# fishnet-0_1.net
KiCad netlist of a schematic drawn in EAGLE
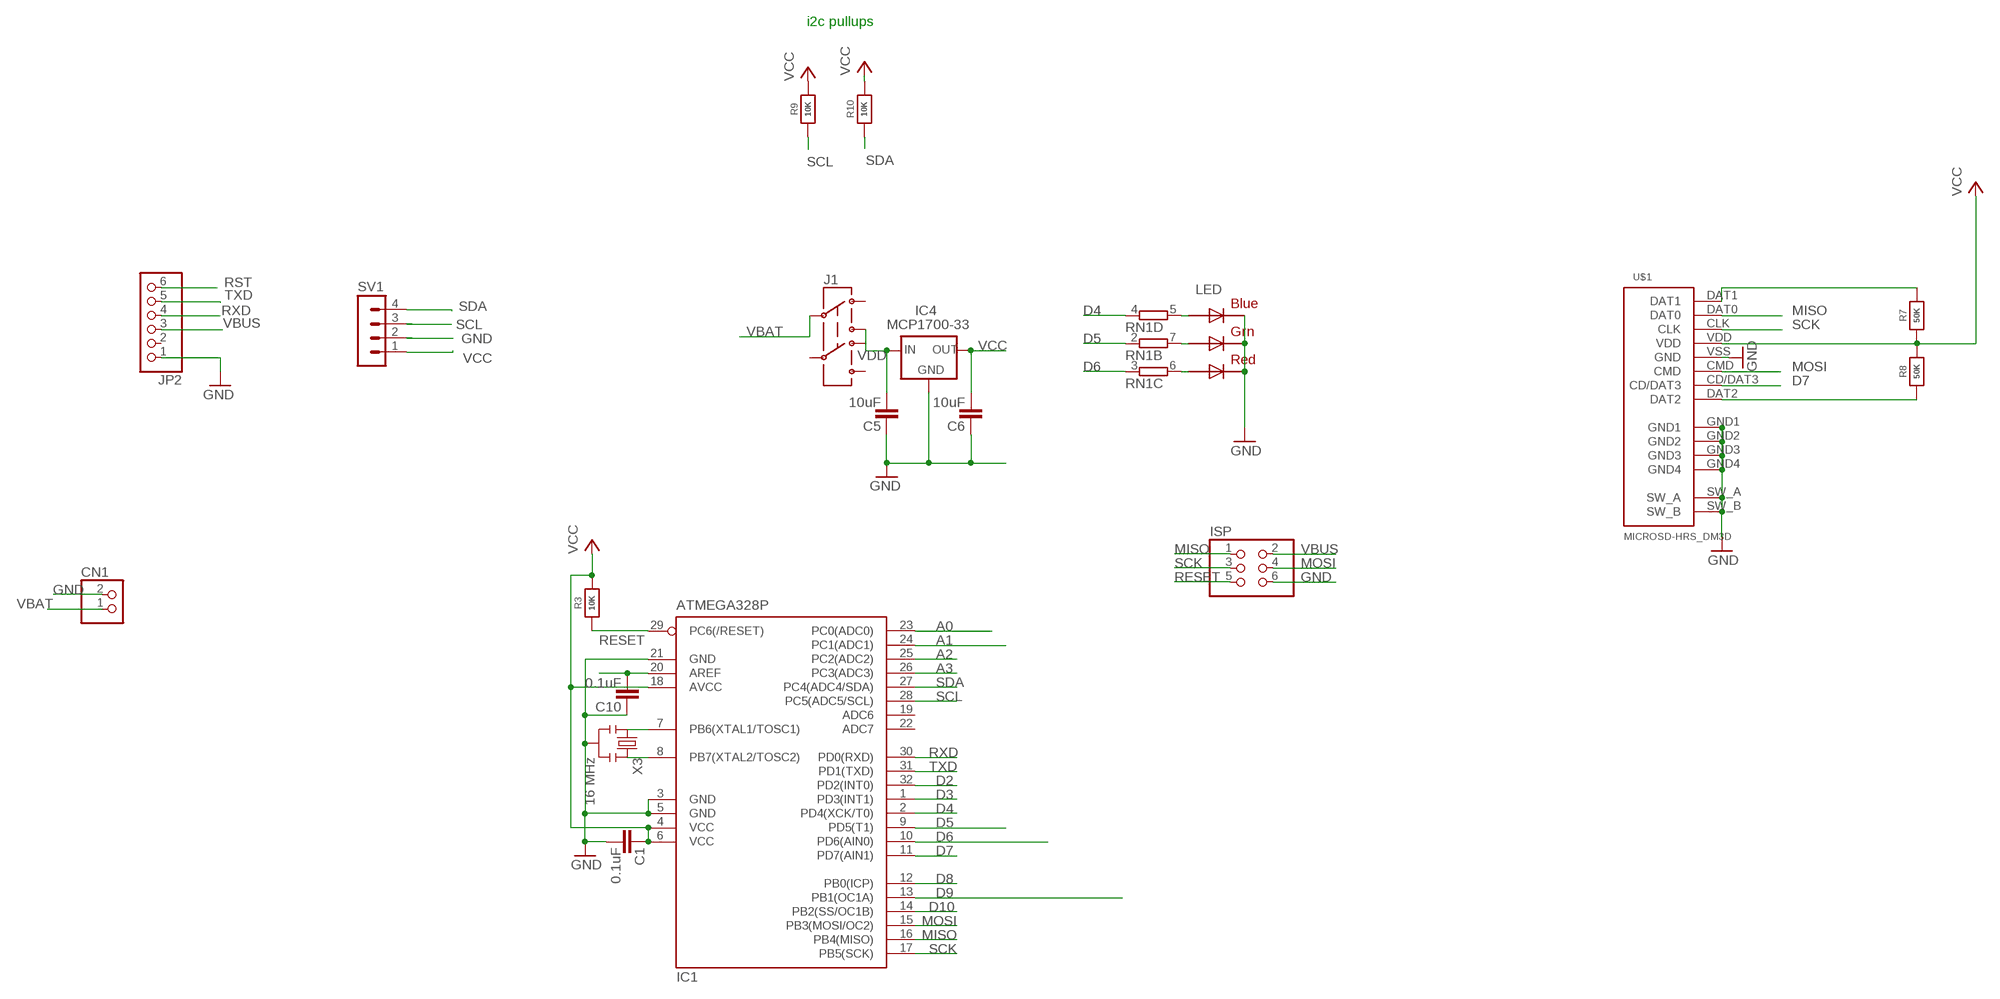
[diagram p0: schematic, sheet 1]

(export (version "E")
  (design (tool "Eeschema 10.0.6"))
  (components
    (comp (ref "C1")
      (value "0.1uF")
      (footprint "eagle-import:0603-CAP")
      (libsource (lib "eagle-import") (part "CAP0603-CAP"))
    )
    (comp (ref "C5")
      (value "10uF")
      (footprint "eagle-import:0603-CAP")
      (libsource (lib "eagle-import") (part "CAP0603-CAP"))
    )
    (comp (ref "C6")
      (value "10uF")
      (footprint "eagle-import:0603-CAP")
      (libsource (lib "eagle-import") (part "CAP0603-CAP"))
    )
    (comp (ref "C10")
      (value "0.1uF")
      (footprint "eagle-import:0603-CAP")
      (libsource (lib "eagle-import") (part "CAP0603-CAP"))
    )
    (comp (ref "CN1")
      (value "JST_2PIN-SMT-RA")
      (footprint "eagle-import:JST-PH-2-SMT-RA")
      (libsource (lib "eagle-import") (part "JST_2PIN-SMT-RA"))
    )
    (comp (ref "IC1")
      (value "ATMEGA328P")
      (footprint "eagle-import:TQFP32-08")
      (fields (field (name "MPN") "ATMEGA8-16AU"))
      (libsource (lib "eagle-import") (part "MEGA8-AI"))
    )
    (comp (ref "IC4")
      (value "MCP1700-33")
      (footprint "eagle-import:SOT89")
      (libsource (lib "eagle-import") (part "MCP1700SOT89"))
    )
    (comp (ref "ISP")
      (value "PINHD-2X3")
      (footprint "eagle-import:2X03")
      (libsource (lib "eagle-import") (part "PINHD-2X3"))
    )
    (comp (ref "J1")
      (value "AYZ0202")
      (footprint "eagle-import:AYZ0202")
      (libsource (lib "eagle-import") (part "AYZ0202"))
    )
    (comp (ref "JP2")
      (value "PINHD-1X6")
      (footprint "eagle-import:1X06")
      (libsource (lib "eagle-import") (part "PINHD-1X6"))
    )
    (comp (ref "LED")
      (value "RGBLED5050")
      (footprint "eagle-import:RGBLED5050")
      (libsource (lib "eagle-import") (part "RGBLED5050"))
    )
    (comp (ref "R3")
      (value "10K")
      (footprint "eagle-import:0603-NO")
      (libsource (lib "eagle-import") (part "RESISTOR_0603_NOOUT"))
    )
    (comp (ref "R7")
      (value "50K")
      (footprint "eagle-import:0603-NO")
      (libsource (lib "eagle-import") (part "RESISTOR_0603_NOOUT"))
    )
    (comp (ref "R8")
      (value "50K")
      (footprint "eagle-import:0603-NO")
      (libsource (lib "eagle-import") (part "RESISTOR_0603_NOOUT"))
    )
    (comp (ref "R9")
      (value "10K")
      (footprint "eagle-import:0603-NO")
      (libsource (lib "eagle-import") (part "RESISTOR_0603_NOOUT"))
    )
    (comp (ref "R10")
      (value "10K")
      (footprint "eagle-import:0603-NO")
      (libsource (lib "eagle-import") (part "RESISTOR_0603_NOOUT"))
    )
    (comp (ref "RN1")
      (value "4R-NEXB38V")
      (footprint "eagle-import:EXB38V")
      (libsource (lib "eagle-import") (part "4R-NEXB38V"))
    )
    (comp (ref "SV1")
      (value "MA04-1")
      (footprint "eagle-import:MA04-1")
      (libsource (lib "eagle-import") (part "MA04-1"))
    )
    (comp (ref "U$1")
      (value "MICROSD-HRS_DM3D")
      (footprint "eagle-import:DM3D")
      (libsource (lib "eagle-import") (part "MICROSD-HRS_DM3D"))
    )
    (comp (ref "X3")
      (value "16 MHz")
      (footprint "eagle-import:RESONATOR-SMD")
      (libsource (lib "eagle-import") (part "RESONATORSMD"))
    )
  )
  (nets
    (net (code "1") (name "/A0") (class "Default")
      (node (ref "IC1") (pin "23") (pinfunction "PC0(ADC0)_23") (pintype "bidirectional"))
    )
    (net (code "2") (name "/A1") (class "Default")
      (node (ref "IC1") (pin "24") (pinfunction "PC1(ADC1)_24") (pintype "bidirectional"))
    )
    (net (code "3") (name "/A2") (class "Default")
      (node (ref "IC1") (pin "25") (pinfunction "PC2(ADC2)_25") (pintype "bidirectional"))
    )
    (net (code "4") (name "/A3") (class "Default")
      (node (ref "IC1") (pin "26") (pinfunction "PC3(ADC3)_26") (pintype "bidirectional"))
    )
    (net (code "5") (name "/D2") (class "Default")
      (node (ref "IC1") (pin "32") (pinfunction "PD2(INT0)_32") (pintype "bidirectional"))
    )
    (net (code "6") (name "/D3") (class "Default")
      (node (ref "IC1") (pin "1") (pinfunction "PD3(INT1)_1") (pintype "bidirectional"))
    )
    (net (code "7") (name "/D4") (class "Default")
      (node (ref "IC1") (pin "2") (pinfunction "PD4(XCK/T0)_2") (pintype "bidirectional"))
      (node (ref "RN1") (pin "4") (pinfunction "1_4") (pintype "passive"))
    )
    (net (code "8") (name "/D5") (class "Default")
      (node (ref "IC1") (pin "9") (pinfunction "PD5(T1)_9") (pintype "bidirectional"))
      (node (ref "RN1") (pin "2") (pinfunction "1_2") (pintype "passive"))
    )
    (net (code "9") (name "/D6") (class "Default")
      (node (ref "IC1") (pin "10") (pinfunction "PD6(AIN0)_10") (pintype "bidirectional"))
      (node (ref "RN1") (pin "3") (pinfunction "1_3") (pintype "passive"))
    )
    (net (code "10") (name "/D7") (class "Default")
      (node (ref "IC1") (pin "11") (pinfunction "PD7(AIN1)_11") (pintype "bidirectional"))
      (node (ref "U$1") (pin "CD/DAT3") (pinfunction "CD/DAT3_CD/DAT3") (pintype "bidirectional"))
    )
    (net (code "11") (name "/D8") (class "Default")
      (node (ref "IC1") (pin "12") (pinfunction "PB0(ICP)_12") (pintype "bidirectional"))
    )
    (net (code "12") (name "/D9") (class "Default")
      (node (ref "IC1") (pin "13") (pinfunction "PB1(OC1A)_13") (pintype "bidirectional"))
    )
    (net (code "13") (name "/D10") (class "Default")
      (node (ref "IC1") (pin "14") (pinfunction "PB2(SS/OC1B)_14") (pintype "bidirectional"))
    )
    (net (code "14") (name "/MISO") (class "Default")
      (node (ref "IC1") (pin "16") (pinfunction "PB4(MISO)_16") (pintype "bidirectional"))
      (node (ref "ISP") (pin "1") (pinfunction "1_1") (pintype "passive"))
      (node (ref "U$1") (pin "DAT0") (pinfunction "DAT0_DAT0") (pintype "bidirectional"))
    )
    (net (code "15") (name "/MOSI") (class "Default")
      (node (ref "IC1") (pin "15") (pinfunction "PB3(MOSI/OC2)_15") (pintype "bidirectional"))
      (node (ref "ISP") (pin "4") (pinfunction "4_4") (pintype "passive"))
      (node (ref "U$1") (pin "CMD") (pinfunction "CMD_CMD") (pintype "bidirectional"))
    )
    (net (code "16") (name "/RESET") (class "Default")
      (node (ref "IC1") (pin "29") (pinfunction "PC6(/RESET)_29") (pintype "bidirectional"))
      (node (ref "ISP") (pin "5") (pinfunction "5_5") (pintype "passive"))
      (node (ref "R3") (pin "1") (pinfunction "1_1") (pintype "passive"))
    )
    (net (code "17") (name "/RST") (class "Default")
      (node (ref "JP2") (pin "6") (pinfunction "6_6") (pintype "passive"))
    )
    (net (code "18") (name "/RXD") (class "Default")
      (node (ref "IC1") (pin "30") (pinfunction "PD0(RXD)_30") (pintype "bidirectional"))
      (node (ref "JP2") (pin "4") (pinfunction "4_4") (pintype "passive"))
    )
    (net (code "19") (name "/SCK") (class "Default")
      (node (ref "IC1") (pin "17") (pinfunction "PB5(SCK)_17") (pintype "bidirectional"))
      (node (ref "ISP") (pin "3") (pinfunction "3_3") (pintype "passive"))
      (node (ref "U$1") (pin "CLK") (pinfunction "CLK_CLK") (pintype "bidirectional"))
    )
    (net (code "20") (name "/SCL") (class "Default")
      (node (ref "IC1") (pin "28") (pinfunction "PC5(ADC5/SCL)_28") (pintype "bidirectional"))
      (node (ref "R9") (pin "1") (pinfunction "1_1") (pintype "passive"))
      (node (ref "SV1") (pin "3") (pinfunction "3_3") (pintype "passive"))
    )
    (net (code "21") (name "/SDA") (class "Default")
      (node (ref "IC1") (pin "27") (pinfunction "PC4(ADC4/SDA)_27") (pintype "bidirectional"))
      (node (ref "R10") (pin "1") (pinfunction "1_1") (pintype "passive"))
      (node (ref "SV1") (pin "4") (pinfunction "4_4") (pintype "passive"))
    )
    (net (code "22") (name "/TXD") (class "Default")
      (node (ref "IC1") (pin "31") (pinfunction "PD1(TXD)_31") (pintype "bidirectional"))
      (node (ref "JP2") (pin "5") (pinfunction "5_5") (pintype "passive"))
    )
    (net (code "23") (name "/VBAT") (class "Default")
      (node (ref "CN1") (pin "1") (pinfunction "2_1") (pintype "passive"))
      (node (ref "J1") (pin "2") (pinfunction "2_2") (pintype "bidirectional"))
    )
    (net (code "24") (name "/VBUS") (class "Default")
      (node (ref "ISP") (pin "2") (pinfunction "2_2") (pintype "passive"))
      (node (ref "JP2") (pin "3") (pinfunction "3_3") (pintype "passive"))
    )
    (net (code "25") (name "/VDD") (class "Default")
      (node (ref "C5") (pin "1") (pinfunction "1_1") (pintype "passive"))
      (node (ref "IC4") (pin "2") (pinfunction "IN_2") (pintype "input"))
      (node (ref "J1") (pin "1") (pinfunction "3_1") (pintype "bidirectional"))
    )
    (net (code "26") (name "GND") (class "Default")
      (node (ref "C1") (pin "1") (pinfunction "1_1") (pintype "passive"))
      (node (ref "C10") (pin "2") (pinfunction "2_2") (pintype "passive"))
      (node (ref "C5") (pin "2") (pinfunction "2_2") (pintype "passive"))
      (node (ref "C6") (pin "2") (pinfunction "2_2") (pintype "passive"))
      (node (ref "CN1") (pin "2") (pinfunction "1_2") (pintype "passive"))
      (node (ref "IC1") (pin "21") (pinfunction "GND_21") (pintype "power_in"))
      (node (ref "IC1") (pin "3") (pinfunction "GND_3") (pintype "power_in"))
      (node (ref "IC1") (pin "5") (pinfunction "GND_5") (pintype "power_in"))
      (node (ref "IC4") (pin "1") (pinfunction "GND_1") (pintype "input"))
      (node (ref "ISP") (pin "6") (pinfunction "6_6") (pintype "passive"))
      (node (ref "JP2") (pin "1") (pinfunction "1_1") (pintype "passive"))
      (node (ref "LED") (pin "4") (pinfunction "BLUE_C_4") (pintype "bidirectional"))
      (node (ref "LED") (pin "5") (pinfunction "RED_C_5") (pintype "bidirectional"))
      (node (ref "LED") (pin "6") (pinfunction "GREEN_C_6") (pintype "bidirectional"))
      (node (ref "SV1") (pin "2") (pinfunction "2_2") (pintype "passive"))
      (node (ref "U$1") (pin "GND1") (pinfunction "GND1_GND1") (pintype "bidirectional"))
      (node (ref "U$1") (pin "GND2") (pinfunction "GND2_GND2") (pintype "bidirectional"))
      (node (ref "U$1") (pin "GND3") (pinfunction "GND3_GND3") (pintype "bidirectional"))
      (node (ref "U$1") (pin "GND4") (pinfunction "GND4_GND4") (pintype "bidirectional"))
      (node (ref "U$1") (pin "SW_A") (pinfunction "SW_A_SW_A") (pintype "bidirectional"))
      (node (ref "U$1") (pin "SW_B") (pinfunction "SW_B_SW_B") (pintype "bidirectional"))
      (node (ref "U$1") (pin "VSS") (pinfunction "GND_VSS") (pintype "bidirectional"))
      (node (ref "X3") (pin "2") (pinfunction "2_2") (pintype "passive"))
    )
    (net (code "27") (name "Net-(IC1-AREF)") (class "Default")
      (node (ref "C10") (pin "1") (pinfunction "1_1") (pintype "passive"))
      (node (ref "IC1") (pin "20") (pinfunction "AREF_20") (pintype "passive"))
    )
    (net (code "28") (name "Net-(IC1-PB6(XTAL1{slash}TOSC1))") (class "Default")
      (node (ref "IC1") (pin "7") (pinfunction "PB6(XTAL1/TOSC1)_7") (pintype "bidirectional"))
      (node (ref "X3") (pin "1") (pinfunction "1_1") (pintype "passive"))
    )
    (net (code "29") (name "Net-(IC1-PB7(XTAL2{slash}TOSC2))") (class "Default")
      (node (ref "IC1") (pin "8") (pinfunction "PB7(XTAL2/TOSC2)_8") (pintype "bidirectional"))
      (node (ref "X3") (pin "3") (pinfunction "3_3") (pintype "passive"))
    )
    (net (code "30") (name "Net-(LED-BLUE_A)") (class "Default")
      (node (ref "LED") (pin "3") (pinfunction "BLUE_A_3") (pintype "bidirectional"))
      (node (ref "RN1") (pin "5") (pinfunction "2_5") (pintype "passive"))
    )
    (net (code "31") (name "Net-(LED-GREEN_A)") (class "Default")
      (node (ref "LED") (pin "1") (pinfunction "GREEN_A_1") (pintype "bidirectional"))
      (node (ref "RN1") (pin "7") (pinfunction "2_7") (pintype "passive"))
    )
    (net (code "32") (name "Net-(LED-RED_A)") (class "Default")
      (node (ref "LED") (pin "2") (pinfunction "RED_A_2") (pintype "bidirectional"))
      (node (ref "RN1") (pin "6") (pinfunction "2_6") (pintype "passive"))
    )
    (net (code "33") (name "Net-(R7-Pad2)") (class "Default")
      (node (ref "R7") (pin "2") (pinfunction "2_2") (pintype "passive"))
      (node (ref "U$1") (pin "DAT1") (pinfunction "DAT1_DAT1") (pintype "bidirectional"))
    )
    (net (code "34") (name "Net-(R8-Pad1)") (class "Default")
      (node (ref "R8") (pin "1") (pinfunction "1_1") (pintype "passive"))
      (node (ref "U$1") (pin "DAT2") (pinfunction "DAT2_DAT2") (pintype "bidirectional"))
    )
    (net (code "35") (name "VCC") (class "Default")
      (node (ref "C1") (pin "2") (pinfunction "2_2") (pintype "passive"))
      (node (ref "C6") (pin "1") (pinfunction "1_1") (pintype "passive"))
      (node (ref "IC1") (pin "18") (pinfunction "AVCC_18") (pintype "power_in"))
      (node (ref "IC1") (pin "4") (pinfunction "VCC_4") (pintype "power_in"))
      (node (ref "IC1") (pin "6") (pinfunction "VCC_6") (pintype "power_in"))
      (node (ref "IC4") (pin "3") (pinfunction "OUT_3") (pintype "passive"))
      (node (ref "R10") (pin "2") (pinfunction "2_2") (pintype "passive"))
      (node (ref "R3") (pin "2") (pinfunction "2_2") (pintype "passive"))
      (node (ref "R7") (pin "1") (pinfunction "1_1") (pintype "passive"))
      (node (ref "R8") (pin "2") (pinfunction "2_2") (pintype "passive"))
      (node (ref "R9") (pin "2") (pinfunction "2_2") (pintype "passive"))
      (node (ref "SV1") (pin "1") (pinfunction "1_1") (pintype "passive"))
      (node (ref "U$1") (pin "VDD") (pinfunction "VDD_VDD") (pintype "bidirectional"))
    )
    (net (code "36") (name "unconnected-(IC1-ADC6-Pad19)") (class "Default")
      (node (ref "IC1") (pin "19") (pinfunction "ADC6_19") (pintype "bidirectional"))
    )
    (net (code "37") (name "unconnected-(IC1-ADC7-Pad22)") (class "Default")
      (node (ref "IC1") (pin "22") (pinfunction "ADC7_22") (pintype "bidirectional"))
    )
    (net (code "38") (name "unconnected-(J1-1-Pad3)") (class "Default")
      (node (ref "J1") (pin "3") (pinfunction "1_3") (pintype "bidirectional"))
    )
    (net (code "39") (name "unconnected-(J1-4-Pad6)") (class "Default")
      (node (ref "J1") (pin "6") (pinfunction "4_6") (pintype "bidirectional"))
    )
    (net (code "40") (name "unconnected-(J1-6-Pad4)") (class "Default")
      (node (ref "J1") (pin "4") (pinfunction "6_4") (pintype "bidirectional"))
    )
    (net (code "41") (name "unconnected-(J1-Pad5)") (class "Default")
      (node (ref "J1") (pin "5") (pinfunction "5_5") (pintype "bidirectional"))
    )
    (net (code "42") (name "unconnected-(JP2-Pad2)") (class "Default")
      (node (ref "JP2") (pin "2") (pinfunction "2_2") (pintype "passive"))
    )
  )
)
